# 01_Power-Core.net
KiCad netlist of a schematic drawn in Altium Designer
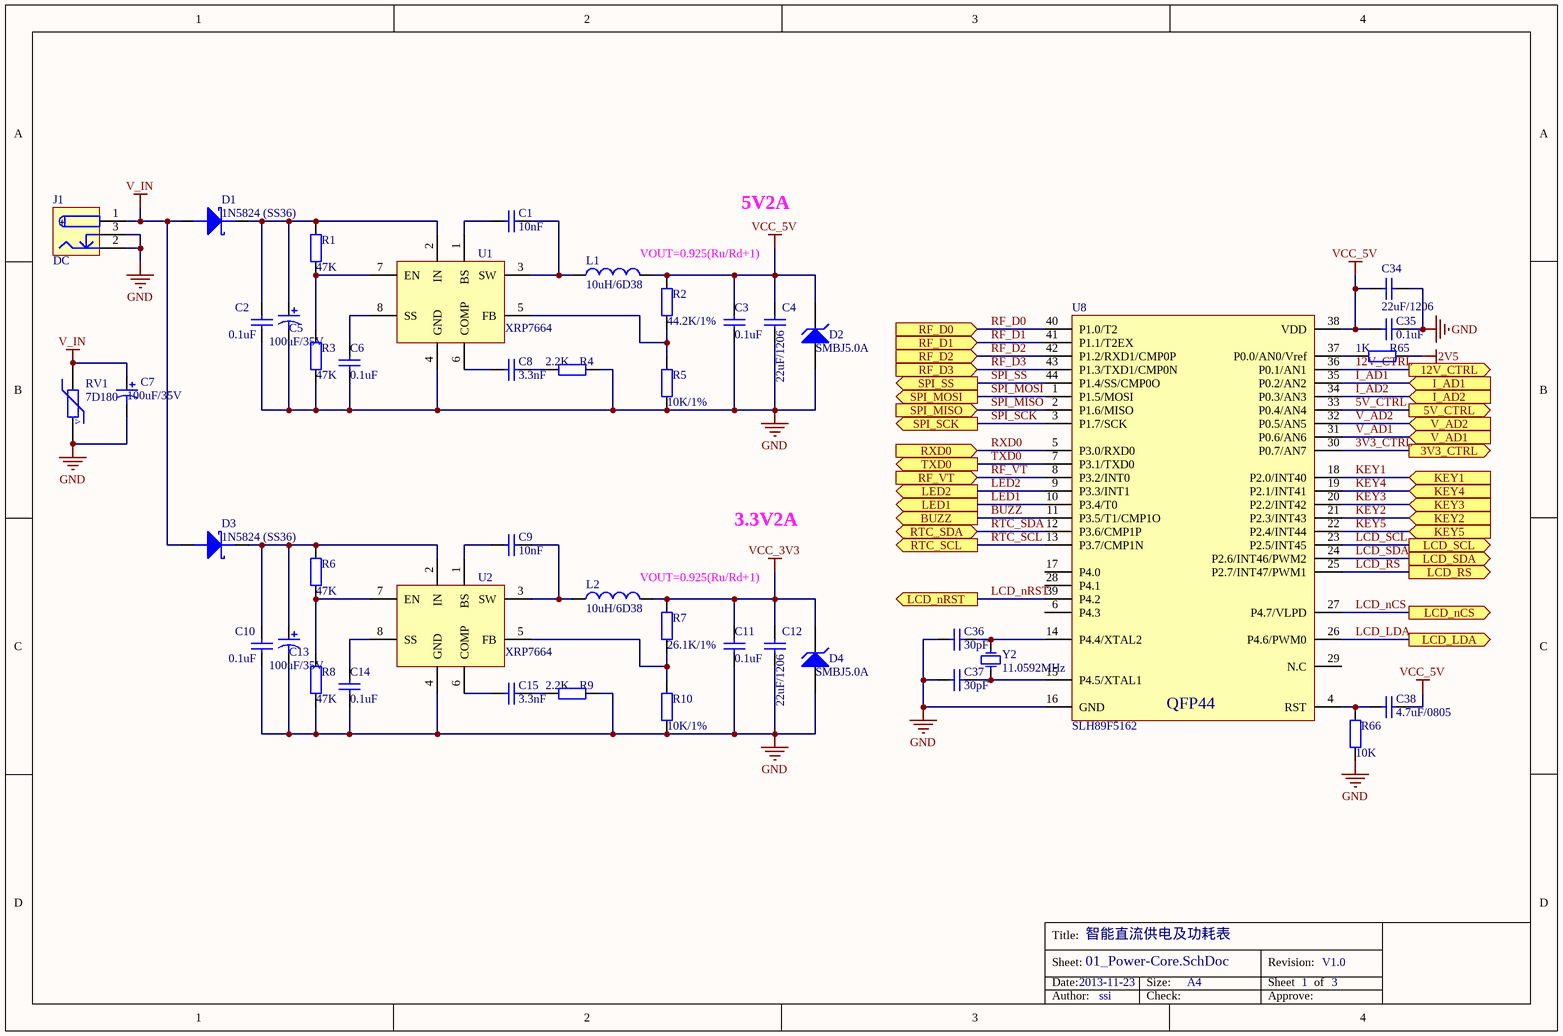
[diagram p0: 01_Power-Core.SchDoc]

(export (version "E")
  (design (tool "Eeschema 10.0.6"))
  (components
    (comp (ref "C1")
      (value "10nF")
      (footprint "0603C")
      (description "Capacitor")
      (fields (field (name "PUBLISHER") "Altium Limited"))
      (libsource (lib "SSD-Schlib1") (part "Cap"))
    )
    (comp (ref "C2")
      (value "0.1uF")
      (footprint "0603C")
      (description "Capacitor")
      (fields (field (name "PUBLISHER") "Altium Limited"))
      (libsource (lib "SSD-Schlib1") (part "Cap"))
    )
    (comp (ref "C3")
      (value "0.1uF")
      (footprint "0603C")
      (description "Capacitor")
      (fields (field (name "PUBLISHER") "Altium Limited"))
      (libsource (lib "SSD-Schlib1") (part "Cap"))
    )
    (comp (ref "C4")
      (value "22uF/1206")
      (footprint "1206")
      (description "Capacitor")
      (fields (field (name "PUBLISHER") "Altium Limited"))
      (libsource (lib "SSD-Schlib1") (part "Cap"))
    )
    (comp (ref "C5")
      (value "100uF/35V")
      (footprint "CAP_6.3X11")
      (description "Capacitor")
      (fields (field (name "PUBLISHER") "Altium Limited"))
      (libsource (lib "SSD-Schlib1") (part "Cap2"))
    )
    (comp (ref "C6")
      (value "0.1uF")
      (footprint "0603C")
      (description "Capacitor")
      (fields (field (name "PUBLISHER") "Altium Limited"))
      (libsource (lib "SSD-Schlib1") (part "Cap"))
    )
    (comp (ref "C7")
      (value "100uF/35V")
      (footprint "CAP_6.3X11")
      (description "Capacitor")
      (fields (field (name "PUBLISHER") "Altium Limited"))
      (libsource (lib "SSD-Schlib1") (part "Cap2"))
    )
    (comp (ref "C8")
      (value "3.3nF")
      (footprint "0603C")
      (description "Capacitor")
      (fields (field (name "PUBLISHER") "Altium Limited"))
      (libsource (lib "SSD-Schlib1") (part "Cap"))
    )
    (comp (ref "C9")
      (value "10nF")
      (footprint "0603C")
      (description "Capacitor")
      (fields (field (name "PUBLISHER") "Altium Limited"))
      (libsource (lib "SSD-Schlib1") (part "Cap"))
    )
    (comp (ref "C10")
      (value "0.1uF")
      (footprint "0603C")
      (description "Capacitor")
      (fields (field (name "PUBLISHER") "Altium Limited"))
      (libsource (lib "SSD-Schlib1") (part "Cap"))
    )
    (comp (ref "C11")
      (value "0.1uF")
      (footprint "0603C")
      (description "Capacitor")
      (fields (field (name "PUBLISHER") "Altium Limited"))
      (libsource (lib "SSD-Schlib1") (part "Cap"))
    )
    (comp (ref "C12")
      (value "22uF/1206")
      (footprint "1206")
      (description "Capacitor")
      (fields (field (name "PUBLISHER") "Altium Limited"))
      (libsource (lib "SSD-Schlib1") (part "Cap"))
    )
    (comp (ref "C13")
      (value "100uF/35V")
      (footprint "CAP_6.3X11")
      (description "Capacitor")
      (fields (field (name "PUBLISHER") "Altium Limited"))
      (libsource (lib "SSD-Schlib1") (part "Cap2"))
    )
    (comp (ref "C14")
      (value "0.1uF")
      (footprint "0603C")
      (description "Capacitor")
      (fields (field (name "PUBLISHER") "Altium Limited"))
      (libsource (lib "SSD-Schlib1") (part "Cap"))
    )
    (comp (ref "C15")
      (value "3.3nF")
      (footprint "0603C")
      (description "Capacitor")
      (fields (field (name "PUBLISHER") "Altium Limited"))
      (libsource (lib "SSD-Schlib1") (part "Cap"))
    )
    (comp (ref "C34")
      (value "22uF/1206")
      (footprint "1206")
      (description "Capacitor")
      (fields (field (name "PUBLISHER") "Altium Limited"))
      (libsource (lib "SSD-Schlib1") (part "Cap"))
    )
    (comp (ref "C35")
      (value "0.1uF")
      (footprint "0603C")
      (description "Capacitor")
      (fields (field (name "PUBLISHER") "Altium Limited"))
      (libsource (lib "SSD-Schlib1") (part "Cap"))
    )
    (comp (ref "C36")
      (value "30pF")
      (footprint "0603C")
      (description "Capacitor")
      (fields (field (name "PUBLISHER") "Altium Limited"))
      (libsource (lib "SSD-Schlib1") (part "Cap"))
    )
    (comp (ref "C37")
      (value "30pF")
      (footprint "0603C")
      (description "Capacitor")
      (fields (field (name "PUBLISHER") "Altium Limited"))
      (libsource (lib "SSD-Schlib1") (part "Cap"))
    )
    (comp (ref "C38")
      (value "4.7uF/0805")
      (footprint "0805")
      (description "Capacitor")
      (fields (field (name "PUBLISHER") "Altium Limited"))
      (libsource (lib "SSD-Schlib1") (part "Cap"))
    )
    (comp (ref "D1")
      (value "1N5824 (SS36)")
      (footprint "SMA/DO-214AC")
      (description "Schottky Diode")
      (libsource (lib "SSD-Schlib1") (part "DIODE_1N582x"))
    )
    (comp (ref "D2")
      (value "SMBJ5.0A")
      (footprint "SMB/DO-214AB")
      (description "Zener Diode")
      (fields (field (name "PUBLISHER") "Altium Limited"))
      (libsource (lib "SSD-Schlib1") (part "DIODE_SMBJxx"))
    )
    (comp (ref "D3")
      (value "1N5824 (SS36)")
      (footprint "SMA/DO-214AC")
      (description "Schottky Diode")
      (libsource (lib "SSD-Schlib1") (part "DIODE_1N582x"))
    )
    (comp (ref "D4")
      (value "SMBJ5.0A")
      (footprint "SMB/DO-214AB")
      (description "Zener Diode")
      (fields (field (name "PUBLISHER") "Altium Limited"))
      (libsource (lib "SSD-Schlib1") (part "DIODE_SMBJxx"))
    )
    (comp (ref "J1")
      (value "DC")
      (footprint "DC5.0mm")
      (description "Low Voltage Power Supply Connector")
      (fields (field (name "PUBLISHER") "Altium Limited"))
      (libsource (lib "SSD-Schlib1") (part "DC_PWR"))
    )
    (comp (ref "L1")
      (value "10uH/6D38")
      (footprint "INDUCTOR-6D38")
      (description "Inductor")
      (fields (field (name "PUBLISHER") "Altium Limited"))
      (libsource (lib "SSD-Schlib1") (part "Inductor"))
    )
    (comp (ref "L2")
      (value "10uH/6D38")
      (footprint "INDUCTOR-6D38")
      (description "Inductor")
      (fields (field (name "PUBLISHER") "Altium Limited"))
      (libsource (lib "SSD-Schlib1") (part "Inductor"))
    )
    (comp (ref "R1")
      (value "47K")
      (footprint "0603")
      (description "Resistor")
      (fields (field (name "PUBLISHER") "Altium Limited"))
      (libsource (lib "SSD-Schlib1") (part "Res2"))
    )
    (comp (ref "R2")
      (value "44.2K/1%")
      (footprint "0603")
      (description "Resistor")
      (fields (field (name "PUBLISHER") "Altium Limited"))
      (libsource (lib "SSD-Schlib1") (part "Res2"))
    )
    (comp (ref "R3")
      (value "47K")
      (footprint "0603")
      (description "Resistor")
      (fields (field (name "PUBLISHER") "Altium Limited"))
      (libsource (lib "SSD-Schlib1") (part "Res2"))
    )
    (comp (ref "R4")
      (value "2.2K")
      (footprint "0603")
      (description "Resistor")
      (fields (field (name "PUBLISHER") "Altium Limited"))
      (libsource (lib "") (part "Res2_1"))
    )
    (comp (ref "R5")
      (value "10K/1%")
      (footprint "0603")
      (description "Resistor")
      (fields (field (name "PUBLISHER") "Altium Limited"))
      (libsource (lib "SSD-Schlib1") (part "Res2"))
    )
    (comp (ref "R6")
      (value "47K")
      (footprint "0603")
      (description "Resistor")
      (fields (field (name "PUBLISHER") "Altium Limited"))
      (libsource (lib "SSD-Schlib1") (part "Res2"))
    )
    (comp (ref "R7")
      (value "26.1K/1%")
      (footprint "0603")
      (description "Resistor")
      (fields (field (name "PUBLISHER") "Altium Limited"))
      (libsource (lib "SSD-Schlib1") (part "Res2"))
    )
    (comp (ref "R8")
      (value "47K")
      (footprint "0603")
      (description "Resistor")
      (fields (field (name "PUBLISHER") "Altium Limited"))
      (libsource (lib "SSD-Schlib1") (part "Res2"))
    )
    (comp (ref "R9")
      (value "2.2K")
      (footprint "0603")
      (description "Resistor")
      (fields (field (name "PUBLISHER") "Altium Limited"))
      (libsource (lib "") (part "Res2_1"))
    )
    (comp (ref "R10")
      (value "10K/1%")
      (footprint "0603")
      (description "Resistor")
      (fields (field (name "PUBLISHER") "Altium Limited"))
      (libsource (lib "SSD-Schlib1") (part "Res2"))
    )
    (comp (ref "R65")
      (value "1K")
      (footprint "0603")
      (description "Resistor")
      (fields (field (name "PUBLISHER") "Altium Limited"))
      (libsource (lib "") (part "Res2_1"))
    )
    (comp (ref "R66")
      (value "10K")
      (footprint "0603")
      (description "Resistor")
      (fields (field (name "PUBLISHER") "Altium Limited"))
      (libsource (lib "SSD-Schlib1") (part "Res2"))
    )
    (comp (ref "RV1")
      (value "7D180")
      (footprint "RV2_7D")
      (description "Varistor (Voltage-Sensitive Resistor) 压敏电阻")
      (fields (field (name "PUBLISHER") "Altium Limited"))
      (libsource (lib "SSD-Schlib1") (part "RES VDR"))
    )
    (comp (ref "U1")
      (value "XRP7664")
      (footprint "SOIC-8")
      (description "2A  18V  Synchronous  Step-Down Converter")
      (libsource (lib "SSD-Schlib1") (part "XRP7664/MP1482"))
    )
    (comp (ref "U2")
      (value "XRP7664")
      (footprint "SOIC-8")
      (description "2A  18V  Synchronous  Step-Down Converter")
      (libsource (lib "SSD-Schlib1") (part "XRP7664/MP1482"))
    )
    (comp (ref "U8")
      (value "SLH89F5162")
      (footprint "LQFP44")
      (libsource (lib "SSD-Schlib1") (part "SLH89F5162_QFP44"))
    )
    (comp (ref "Y2")
      (value "11.0592MHz")
      (footprint "XTAL")
      (description "Crystal Oscillator")
      (fields (field (name "PUBLISHER") "Altium Limited"))
      (libsource (lib "SSD-Schlib1") (part "XTAL"))
    )
  )
  (nets
    (net (code "1") (name "/3V3_CTRL") (class "Default")
      (node (ref "U8") (pin "30") (pinfunction "P0.7/AN7_30") (pintype "passive"))
    )
    (net (code "2") (name "/5V_CTRL") (class "Default")
      (node (ref "U8") (pin "33") (pinfunction "P0.4/AN4_33") (pintype "passive"))
    )
    (net (code "3") (name "/12V_CTRL") (class "Default")
      (node (ref "U8") (pin "36") (pinfunction "P0.1/AN1_36") (pintype "passive"))
    )
    (net (code "4") (name "/BUZZ") (class "Default")
      (node (ref "U8") (pin "11") (pinfunction "P3.5/T1/CMP1O_11") (pintype "passive"))
    )
    (net (code "5") (name "/I_AD1") (class "Default")
      (node (ref "U8") (pin "35") (pinfunction "P0.2/AN2_35") (pintype "passive"))
    )
    (net (code "6") (name "/I_AD2") (class "Default")
      (node (ref "U8") (pin "34") (pinfunction "P0.3/AN3_34") (pintype "passive"))
    )
    (net (code "7") (name "/KEY1") (class "Default")
      (node (ref "U8") (pin "18") (pinfunction "P2.0/INT40_18") (pintype "passive"))
    )
    (net (code "8") (name "/KEY2") (class "Default")
      (node (ref "U8") (pin "21") (pinfunction "P2.3/INT43_21") (pintype "passive"))
    )
    (net (code "9") (name "/KEY3") (class "Default")
      (node (ref "U8") (pin "20") (pinfunction "P2.2/INT42_20") (pintype "passive"))
    )
    (net (code "10") (name "/KEY4") (class "Default")
      (node (ref "U8") (pin "19") (pinfunction "P2.1/INT41_19") (pintype "passive"))
    )
    (net (code "11") (name "/KEY5") (class "Default")
      (node (ref "U8") (pin "22") (pinfunction "P2.4/INT44_22") (pintype "passive"))
    )
    (net (code "12") (name "/LCD_LDA") (class "Default")
      (node (ref "U8") (pin "26") (pinfunction "P4.6/PWM0_26") (pintype "passive"))
    )
    (net (code "13") (name "/LCD_RS") (class "Default")
      (node (ref "U8") (pin "25") (pinfunction "P2.7/INT47/PWM1_25") (pintype "passive"))
    )
    (net (code "14") (name "/LCD_SCL") (class "Default")
      (node (ref "U8") (pin "23") (pinfunction "P2.5/INT45_23") (pintype "passive"))
    )
    (net (code "15") (name "/LCD_SDA") (class "Default")
      (node (ref "U8") (pin "24") (pinfunction "P2.6/INT46/PWM2_24") (pintype "passive"))
    )
    (net (code "16") (name "/LCD_nCS") (class "Default")
      (node (ref "U8") (pin "27") (pinfunction "P4.7/VLPD_27") (pintype "passive"))
    )
    (net (code "17") (name "/LCD_nRST") (class "Default")
      (node (ref "U8") (pin "39") (pinfunction "P4.2_39") (pintype "passive"))
    )
    (net (code "18") (name "/LED1") (class "Default")
      (node (ref "U8") (pin "10") (pinfunction "P3.4/T0_10") (pintype "passive"))
    )
    (net (code "19") (name "/LED2") (class "Default")
      (node (ref "U8") (pin "9") (pinfunction "P3.3/INT1_9") (pintype "passive"))
    )
    (net (code "20") (name "/RF_D0") (class "Default")
      (node (ref "U8") (pin "40") (pinfunction "P1.0/T2_40") (pintype "passive"))
    )
    (net (code "21") (name "/RF_D1") (class "Default")
      (node (ref "U8") (pin "41") (pinfunction "P1.1/T2EX_41") (pintype "passive"))
    )
    (net (code "22") (name "/RF_D2") (class "Default")
      (node (ref "U8") (pin "42") (pinfunction "P1.2/RXD1/CMP0P_42") (pintype "passive"))
    )
    (net (code "23") (name "/RF_D3") (class "Default")
      (node (ref "U8") (pin "43") (pinfunction "P1.3/TXD1/CMP0N_43") (pintype "passive"))
    )
    (net (code "24") (name "/RF_VT") (class "Default")
      (node (ref "U8") (pin "8") (pinfunction "P3.2/INT0_8") (pintype "passive"))
    )
    (net (code "25") (name "/RTC_SCL") (class "Default")
      (node (ref "U8") (pin "13") (pinfunction "P3.7/CMP1N_13") (pintype "passive"))
    )
    (net (code "26") (name "/RTC_SDA") (class "Default")
      (node (ref "U8") (pin "12") (pinfunction "P3.6/CMP1P_12") (pintype "passive"))
    )
    (net (code "27") (name "/RXD0") (class "Default")
      (node (ref "U8") (pin "5") (pinfunction "P3.0/RXD0_5") (pintype "passive"))
    )
    (net (code "28") (name "/SPI_MISO") (class "Default")
      (node (ref "U8") (pin "2") (pinfunction "P1.6/MISO_2") (pintype "passive"))
    )
    (net (code "29") (name "/SPI_MOSI") (class "Default")
      (node (ref "U8") (pin "1") (pinfunction "P1.5/MOSI_1") (pintype "passive"))
    )
    (net (code "30") (name "/SPI_SCK") (class "Default")
      (node (ref "U8") (pin "3") (pinfunction "P1.7/SCK_3") (pintype "passive"))
    )
    (net (code "31") (name "/SPI_SS") (class "Default")
      (node (ref "U8") (pin "44") (pinfunction "P1.4/SS/CMP0O_44") (pintype "passive"))
    )
    (net (code "32") (name "/TXD0") (class "Default")
      (node (ref "U8") (pin "7") (pinfunction "P3.1/TXD0_7") (pintype "passive"))
    )
    (net (code "33") (name "/V_AD1") (class "Default")
      (node (ref "U8") (pin "31") (pinfunction "P0.6/AN6_31") (pintype "passive"))
    )
    (net (code "34") (name "/V_AD2") (class "Default")
      (node (ref "U8") (pin "32") (pinfunction "P0.5/AN5_32") (pintype "passive"))
    )
    (net (code "35") (name "2V5") (class "Default")
      (node (ref "R65") (pin "2") (pinfunction "2_2") (pintype "passive"))
    )
    (net (code "36") (name "GND") (class "Default")
      (node (ref "C10") (pin "1") (pinfunction "1_1") (pintype "passive"))
      (node (ref "C11") (pin "1") (pinfunction "1_1") (pintype "passive"))
      (node (ref "C12") (pin "1") (pinfunction "1_1") (pintype "passive"))
      (node (ref "C13") (pin "2") (pinfunction "2_2") (pintype "passive"))
      (node (ref "C14") (pin "1") (pinfunction "1_1") (pintype "passive"))
      (node (ref "C2") (pin "1") (pinfunction "1_1") (pintype "passive"))
      (node (ref "C3") (pin "1") (pinfunction "1_1") (pintype "passive"))
      (node (ref "C34") (pin "1") (pinfunction "1_1") (pintype "passive"))
      (node (ref "C35") (pin "2") (pinfunction "2_2") (pintype "passive"))
      (node (ref "C36") (pin "1") (pinfunction "1_1") (pintype "passive"))
      (node (ref "C37") (pin "1") (pinfunction "1_1") (pintype "passive"))
      (node (ref "C4") (pin "1") (pinfunction "1_1") (pintype "passive"))
      (node (ref "C5") (pin "2") (pinfunction "2_2") (pintype "passive"))
      (node (ref "C6") (pin "1") (pinfunction "1_1") (pintype "passive"))
      (node (ref "C7") (pin "2") (pinfunction "2_2") (pintype "passive"))
      (node (ref "D2") (pin "1") (pinfunction "A_1") (pintype "passive"))
      (node (ref "D4") (pin "1") (pinfunction "A_1") (pintype "passive"))
      (node (ref "J1") (pin "2") (pinfunction "-_2") (pintype "power_in"))
      (node (ref "J1") (pin "3") (pinfunction "W_3") (pintype "power_in"))
      (node (ref "R10") (pin "1") (pinfunction "1_1") (pintype "passive"))
      (node (ref "R3") (pin "1") (pinfunction "1_1") (pintype "passive"))
      (node (ref "R4") (pin "2") (pinfunction "2_2") (pintype "passive"))
      (node (ref "R5") (pin "1") (pinfunction "1_1") (pintype "passive"))
      (node (ref "R66") (pin "1") (pinfunction "1_1") (pintype "passive"))
      (node (ref "R8") (pin "1") (pinfunction "1_1") (pintype "passive"))
      (node (ref "R9") (pin "2") (pinfunction "2_2") (pintype "passive"))
      (node (ref "RV1") (pin "1") (pinfunction "1_1") (pintype "passive"))
      (node (ref "U1") (pin "4") (pinfunction "GND_4") (pintype "power_in"))
      (node (ref "U2") (pin "4") (pinfunction "GND_4") (pintype "power_in"))
      (node (ref "U8") (pin "16") (pinfunction "GND_16") (pintype "power_in"))
    )
    (net (code "37") (name "Net-(C8-Pad2)") (class "Default")
      (node (ref "C8") (pin "2") (pinfunction "2_2") (pintype "passive"))
      (node (ref "R4") (pin "1") (pinfunction "1_1") (pintype "passive"))
    )
    (net (code "38") (name "Net-(C15-Pad2)") (class "Default")
      (node (ref "C15") (pin "2") (pinfunction "2_2") (pintype "passive"))
      (node (ref "R9") (pin "1") (pinfunction "1_1") (pintype "passive"))
    )
    (net (code "39") (name "Net-(D1-K)") (class "Default")
      (node (ref "C2") (pin "2") (pinfunction "2_2") (pintype "passive"))
      (node (ref "C5") (pin "1") (pinfunction "1_1") (pintype "passive"))
      (node (ref "D1") (pin "2") (pinfunction "K_2") (pintype "passive"))
      (node (ref "R1") (pin "2") (pinfunction "2_2") (pintype "passive"))
      (node (ref "U1") (pin "2") (pinfunction "IN_2") (pintype "passive"))
    )
    (net (code "40") (name "Net-(D3-K)") (class "Default")
      (node (ref "C10") (pin "2") (pinfunction "2_2") (pintype "passive"))
      (node (ref "C13") (pin "1") (pinfunction "1_1") (pintype "passive"))
      (node (ref "D3") (pin "2") (pinfunction "K_2") (pintype "passive"))
      (node (ref "R6") (pin "2") (pinfunction "2_2") (pintype "passive"))
      (node (ref "U2") (pin "2") (pinfunction "IN_2") (pintype "passive"))
    )
    (net (code "41") (name "Net-(U1-BS)") (class "Default")
      (node (ref "C1") (pin "1") (pinfunction "1_1") (pintype "passive"))
      (node (ref "U1") (pin "1") (pinfunction "BS_1") (pintype "passive"))
    )
    (net (code "42") (name "Net-(U1-COMP)") (class "Default")
      (node (ref "C8") (pin "1") (pinfunction "1_1") (pintype "passive"))
      (node (ref "U1") (pin "6") (pinfunction "COMP_6") (pintype "passive"))
    )
    (net (code "43") (name "Net-(U1-EN)") (class "Default")
      (node (ref "R1") (pin "1") (pinfunction "1_1") (pintype "passive"))
      (node (ref "R3") (pin "2") (pinfunction "2_2") (pintype "passive"))
      (node (ref "U1") (pin "7") (pinfunction "EN_7") (pintype "passive"))
    )
    (net (code "44") (name "Net-(U1-FB)") (class "Default")
      (node (ref "R2") (pin "1") (pinfunction "1_1") (pintype "passive"))
      (node (ref "R5") (pin "2") (pinfunction "2_2") (pintype "passive"))
      (node (ref "U1") (pin "5") (pinfunction "FB_5") (pintype "passive"))
    )
    (net (code "45") (name "Net-(U1-SS)") (class "Default")
      (node (ref "C6") (pin "2") (pinfunction "2_2") (pintype "passive"))
      (node (ref "U1") (pin "8") (pinfunction "SS_8") (pintype "passive"))
    )
    (net (code "46") (name "Net-(U1-SW)") (class "Default")
      (node (ref "C1") (pin "2") (pinfunction "2_2") (pintype "passive"))
      (node (ref "L1") (pin "1") (pinfunction "1_1") (pintype "passive"))
      (node (ref "U1") (pin "3") (pinfunction "SW_3") (pintype "passive"))
    )
    (net (code "47") (name "Net-(U2-BS)") (class "Default")
      (node (ref "C9") (pin "1") (pinfunction "1_1") (pintype "passive"))
      (node (ref "U2") (pin "1") (pinfunction "BS_1") (pintype "passive"))
    )
    (net (code "48") (name "Net-(U2-COMP)") (class "Default")
      (node (ref "C15") (pin "1") (pinfunction "1_1") (pintype "passive"))
      (node (ref "U2") (pin "6") (pinfunction "COMP_6") (pintype "passive"))
    )
    (net (code "49") (name "Net-(U2-EN)") (class "Default")
      (node (ref "R6") (pin "1") (pinfunction "1_1") (pintype "passive"))
      (node (ref "R8") (pin "2") (pinfunction "2_2") (pintype "passive"))
      (node (ref "U2") (pin "7") (pinfunction "EN_7") (pintype "passive"))
    )
    (net (code "50") (name "Net-(U2-FB)") (class "Default")
      (node (ref "R10") (pin "2") (pinfunction "2_2") (pintype "passive"))
      (node (ref "R7") (pin "1") (pinfunction "1_1") (pintype "passive"))
      (node (ref "U2") (pin "5") (pinfunction "FB_5") (pintype "passive"))
    )
    (net (code "51") (name "Net-(U2-SS)") (class "Default")
      (node (ref "C14") (pin "2") (pinfunction "2_2") (pintype "passive"))
      (node (ref "U2") (pin "8") (pinfunction "SS_8") (pintype "passive"))
    )
    (net (code "52") (name "Net-(U2-SW)") (class "Default")
      (node (ref "C9") (pin "2") (pinfunction "2_2") (pintype "passive"))
      (node (ref "L2") (pin "1") (pinfunction "1_1") (pintype "passive"))
      (node (ref "U2") (pin "3") (pinfunction "SW_3") (pintype "passive"))
    )
    (net (code "53") (name "Net-(U8-P0.0{slash}AN0{slash}Vref)") (class "Default")
      (node (ref "R65") (pin "1") (pinfunction "1_1") (pintype "passive"))
      (node (ref "U8") (pin "37") (pinfunction "P0.0/AN0/Vref_37") (pintype "passive"))
    )
    (net (code "54") (name "Net-(U8-P4.4{slash}XTAL2)") (class "Default")
      (node (ref "C36") (pin "2") (pinfunction "2_2") (pintype "passive"))
      (node (ref "U8") (pin "14") (pinfunction "P4.4/XTAL2_14") (pintype "passive"))
      (node (ref "Y2") (pin "2") (pinfunction "OSC2_2") (pintype "passive"))
    )
    (net (code "55") (name "Net-(U8-P4.5{slash}XTAL1)") (class "Default")
      (node (ref "C37") (pin "2") (pinfunction "2_2") (pintype "passive"))
      (node (ref "U8") (pin "15") (pinfunction "P4.5/XTAL1_15") (pintype "passive"))
      (node (ref "Y2") (pin "1") (pinfunction "OSC1_1") (pintype "passive"))
    )
    (net (code "56") (name "Net-(U8-RST)") (class "Default")
      (node (ref "C38") (pin "2") (pinfunction "2_2") (pintype "passive"))
      (node (ref "R66") (pin "2") (pinfunction "2_2") (pintype "passive"))
      (node (ref "U8") (pin "4") (pinfunction "RST_4") (pintype "passive"))
    )
    (net (code "57") (name "VCC_3V3") (class "Default")
      (node (ref "C11") (pin "2") (pinfunction "2_2") (pintype "passive"))
      (node (ref "C12") (pin "2") (pinfunction "2_2") (pintype "passive"))
      (node (ref "D4") (pin "2") (pinfunction "K_2") (pintype "passive"))
      (node (ref "L2") (pin "2") (pinfunction "2_2") (pintype "passive"))
      (node (ref "R7") (pin "2") (pinfunction "2_2") (pintype "passive"))
    )
    (net (code "58") (name "VCC_5V") (class "Default")
      (node (ref "C3") (pin "2") (pinfunction "2_2") (pintype "passive"))
      (node (ref "C34") (pin "2") (pinfunction "2_2") (pintype "passive"))
      (node (ref "C35") (pin "1") (pinfunction "1_1") (pintype "passive"))
      (node (ref "C38") (pin "1") (pinfunction "1_1") (pintype "passive"))
      (node (ref "C4") (pin "2") (pinfunction "2_2") (pintype "passive"))
      (node (ref "D2") (pin "2") (pinfunction "K_2") (pintype "passive"))
      (node (ref "L1") (pin "2") (pinfunction "2_2") (pintype "passive"))
      (node (ref "R2") (pin "2") (pinfunction "2_2") (pintype "passive"))
      (node (ref "U8") (pin "38") (pinfunction "VDD_38") (pintype "power_in"))
    )
    (net (code "59") (name "V_IN") (class "Default")
      (node (ref "C7") (pin "1") (pinfunction "1_1") (pintype "passive"))
      (node (ref "D1") (pin "1") (pinfunction "A_1") (pintype "passive"))
      (node (ref "D3") (pin "1") (pinfunction "A_1") (pintype "passive"))
      (node (ref "J1") (pin "1") (pinfunction "+_1") (pintype "power_in"))
      (node (ref "RV1") (pin "2") (pinfunction "2_2") (pintype "passive"))
    )
    (net (code "60") (name "unconnected-(U8-N.C-Pad29)") (class "Default")
      (node (ref "U8") (pin "29") (pinfunction "N.C_29") (pintype "passive"))
    )
    (net (code "61") (name "unconnected-(U8-P4.0-Pad17)") (class "Default")
      (node (ref "U8") (pin "17") (pinfunction "P4.0_17") (pintype "passive"))
    )
    (net (code "62") (name "unconnected-(U8-P4.1-Pad28)") (class "Default")
      (node (ref "U8") (pin "28") (pinfunction "P4.1_28") (pintype "passive"))
    )
    (net (code "63") (name "unconnected-(U8-P4.3-Pad6)") (class "Default")
      (node (ref "U8") (pin "6") (pinfunction "P4.3_6") (pintype "passive"))
    )
  )
)
